# DAC_GainOutputStage4.net
KiCad netlist of a schematic drawn in EAGLE
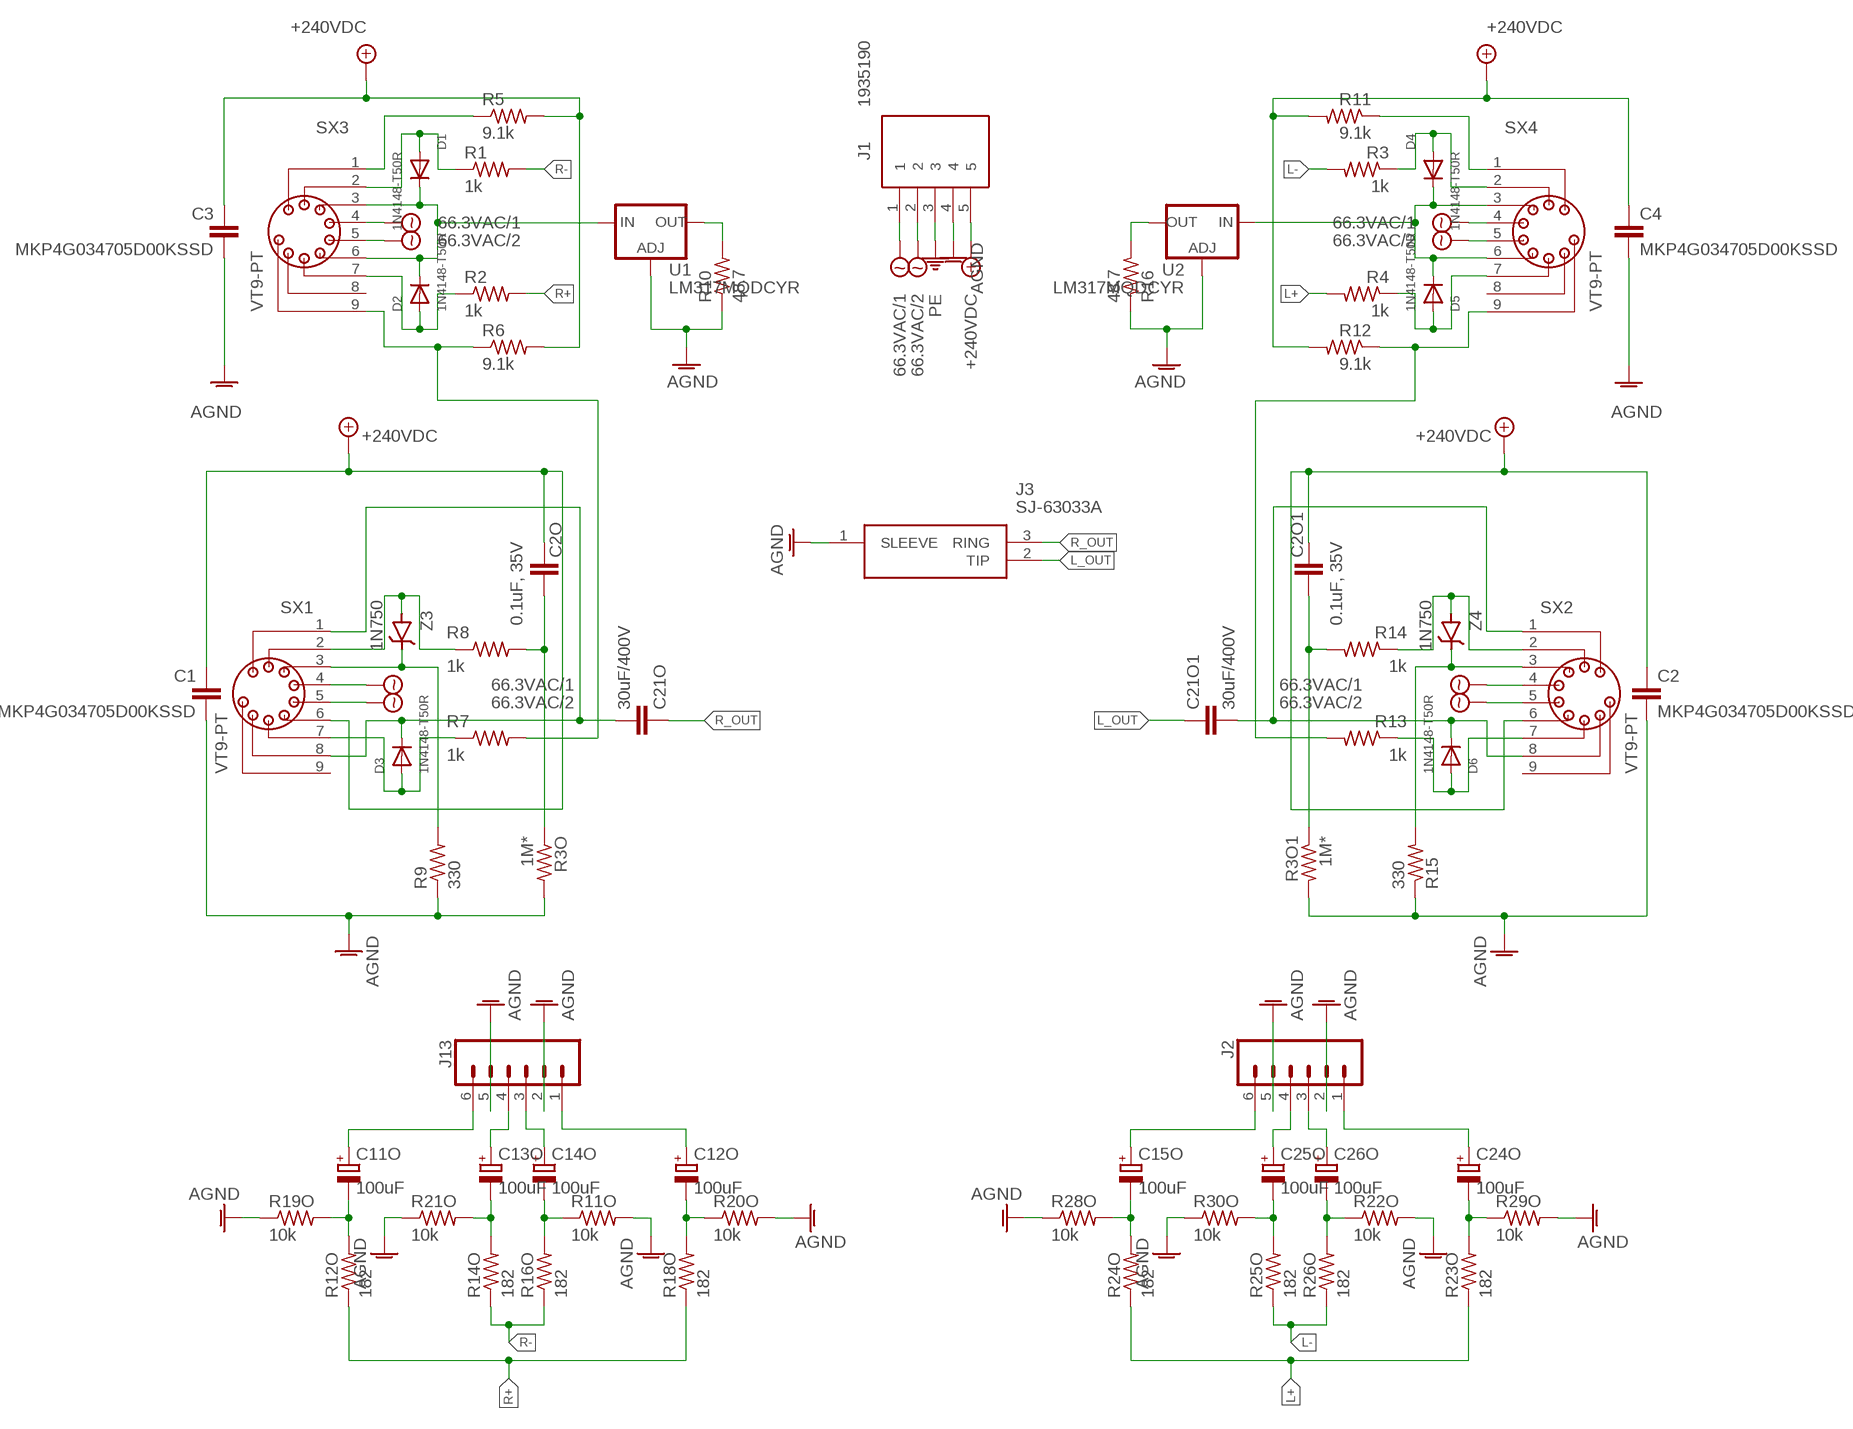
[diagram p0: schematic, sheet 1]

(export (version "E")
  (design (tool "Eeschema 10.0.6"))
  (components
    (comp (ref "C1")
      (value "MKP4G034705D00KSSD")
      (footprint "eagle-import:MKP4G034705D00KSSD")
      (fields (field (name "MOUSER_PART_NUMBER") "505-MKP4G034705DKSSD"))
      (libsource (lib "eagle-import") (part "MKP4G034705D00KSSD"))
    )
    (comp (ref "C2")
      (value "MKP4G034705D00KSSD")
      (footprint "eagle-import:MKP4G034705D00KSSD")
      (fields (field (name "MOUSER_PART_NUMBER") "505-MKP4G034705DKSSD"))
      (libsource (lib "eagle-import") (part "MKP4G034705D00KSSD"))
    )
    (comp (ref "C2O")
      (value "0.1uF, 35V")
      (footprint "eagle-import:MKS4B031002A00JC00")
      (fields
        (field (name "MANUFACTURER_PART_NUMBER") "MKS4B031002A00JC00")
        (field (name "MOUSER_PART_NUMBER") "505-MKS4B0312AJC")
      )
      (libsource (lib "eagle-import") (part "MKS4B031002A00JC00"))
    )
    (comp (ref "C2O1")
      (value "0.1uF, 35V")
      (footprint "eagle-import:MKS4B031002A00JC00")
      (fields
        (field (name "MANUFACTURER_PART_NUMBER") "MKS4B031002A00JC00")
        (field (name "MOUSER_PART_NUMBER") "505-MKS4B0312AJC")
      )
      (libsource (lib "eagle-import") (part "MKS4B031002A00JC00"))
    )
    (comp (ref "C3")
      (value "MKP4G034705D00KSSD")
      (footprint "eagle-import:MKP4G034705D00KSSD")
      (fields (field (name "MOUSER_PART_NUMBER") "505-MKP4G034705DKSSD"))
      (libsource (lib "eagle-import") (part "MKP4G034705D00KSSD"))
    )
    (comp (ref "C4")
      (value "MKP4G034705D00KSSD")
      (footprint "eagle-import:MKP4G034705D00KSSD")
      (fields (field (name "MOUSER_PART_NUMBER") "505-MKP4G034705DKSSD"))
      (libsource (lib "eagle-import") (part "MKP4G034705D00KSSD"))
    )
    (comp (ref "C11O")
      (value "100uF")
      (footprint "eagle-import:CAPPRD350W60D825H1300")
      (fields
        (field (name "ARROW_PART_NUMBER") "UFW1H101MPD1TD")
        (field (name "MOUSER_PART_NUMBER") "647-UFW1H101MPD1TD")
      )
      (libsource (lib "eagle-import") (part "UFW1H101MPD1TD"))
    )
    (comp (ref "C12O")
      (value "100uF")
      (footprint "eagle-import:CAPPRD350W60D825H1300")
      (fields
        (field (name "ARROW_PART_NUMBER") "UFW1H101MPD1TD")
        (field (name "MOUSER_PART_NUMBER") "647-UFW1H101MPD1TD")
      )
      (libsource (lib "eagle-import") (part "UFW1H101MPD1TD"))
    )
    (comp (ref "C13O")
      (value "100uF")
      (footprint "eagle-import:CAPPRD350W60D825H1300")
      (fields
        (field (name "ARROW_PART_NUMBER") "UFW1H101MPD1TD")
        (field (name "MOUSER_PART_NUMBER") "647-UFW1H101MPD1TD")
      )
      (libsource (lib "eagle-import") (part "UFW1H101MPD1TD"))
    )
    (comp (ref "C14O")
      (value "100uF")
      (footprint "eagle-import:CAPPRD350W60D825H1300")
      (fields
        (field (name "ARROW_PART_NUMBER") "UFW1H101MPD1TD")
        (field (name "MOUSER_PART_NUMBER") "647-UFW1H101MPD1TD")
      )
      (libsource (lib "eagle-import") (part "UFW1H101MPD1TD"))
    )
    (comp (ref "C15O")
      (value "100uF")
      (footprint "eagle-import:CAPPRD350W60D825H1300")
      (fields
        (field (name "ARROW_PART_NUMBER") "UFW1H101MPD1TD")
        (field (name "MOUSER_PART_NUMBER") "647-UFW1H101MPD1TD")
      )
      (libsource (lib "eagle-import") (part "UFW1H101MPD1TD"))
    )
    (comp (ref "C21O")
      (value "30uF/400V")
      (footprint "eagle-import:DCP4G053006ID2KSSD")
      (fields
        (field (name "MANUFACTURER_PART_NUMBER") "DCP4G053006ID2KSSD")
        (field (name "MOUSER_PART_NUMBER") "505-DCP4G0536ID2KSSD")
      )
      (libsource (lib "eagle-import") (part "DCP4G053006ID2KSSD"))
    )
    (comp (ref "C21O1")
      (value "30uF/400V")
      (footprint "eagle-import:DCP4G053006ID2KSSD")
      (fields
        (field (name "MANUFACTURER_PART_NUMBER") "DCP4G053006ID2KSSD")
        (field (name "MOUSER_PART_NUMBER") "505-DCP4G0536ID2KSSD")
      )
      (libsource (lib "eagle-import") (part "DCP4G053006ID2KSSD"))
    )
    (comp (ref "C24O")
      (value "100uF")
      (footprint "eagle-import:CAPPRD350W60D825H1300")
      (fields
        (field (name "ARROW_PART_NUMBER") "UFW1H101MPD1TD")
        (field (name "MOUSER_PART_NUMBER") "647-UFW1H101MPD1TD")
      )
      (libsource (lib "eagle-import") (part "UFW1H101MPD1TD"))
    )
    (comp (ref "C25O")
      (value "100uF")
      (footprint "eagle-import:CAPPRD350W60D825H1300")
      (fields
        (field (name "ARROW_PART_NUMBER") "UFW1H101MPD1TD")
        (field (name "MOUSER_PART_NUMBER") "647-UFW1H101MPD1TD")
      )
      (libsource (lib "eagle-import") (part "UFW1H101MPD1TD"))
    )
    (comp (ref "C26O")
      (value "100uF")
      (footprint "eagle-import:CAPPRD350W60D825H1300")
      (fields
        (field (name "ARROW_PART_NUMBER") "UFW1H101MPD1TD")
        (field (name "MOUSER_PART_NUMBER") "647-UFW1H101MPD1TD")
      )
      (libsource (lib "eagle-import") (part "UFW1H101MPD1TD"))
    )
    (comp (ref "D1")
      (value "1N4148-T50R")
      (footprint "eagle-import:DIOAD1068W53L380D172")
      (fields (field (name "MOUSER_PART_NUMBER") "512-1N4148T50R"))
      (libsource (lib "eagle-import") (part "1N4148-T50R"))
    )
    (comp (ref "D2")
      (value "1N4148-T50R")
      (footprint "eagle-import:DIOAD1068W53L380D172")
      (fields (field (name "MOUSER_PART_NUMBER") "512-1N4148T50R"))
      (libsource (lib "eagle-import") (part "1N4148-T50R"))
    )
    (comp (ref "D3")
      (value "1N4148-T50R")
      (footprint "eagle-import:DIOAD1068W53L380D172")
      (fields (field (name "MOUSER_PART_NUMBER") "512-1N4148T50R"))
      (libsource (lib "eagle-import") (part "1N4148-T50R"))
    )
    (comp (ref "D4")
      (value "1N4148-T50R")
      (footprint "eagle-import:DIOAD1068W53L380D172")
      (fields (field (name "MOUSER_PART_NUMBER") "512-1N4148T50R"))
      (libsource (lib "eagle-import") (part "1N4148-T50R"))
    )
    (comp (ref "D5")
      (value "1N4148-T50R")
      (footprint "eagle-import:DIOAD1068W53L380D172")
      (fields (field (name "MOUSER_PART_NUMBER") "512-1N4148T50R"))
      (libsource (lib "eagle-import") (part "1N4148-T50R"))
    )
    (comp (ref "D6")
      (value "1N4148-T50R")
      (footprint "eagle-import:DIOAD1068W53L380D172")
      (fields (field (name "MOUSER_PART_NUMBER") "512-1N4148T50R"))
      (libsource (lib "eagle-import") (part "1N4148-T50R"))
    )
    (comp (ref "J1")
      (value "1935190")
      (footprint "eagle-import:1935190")
      (fields (field (name "MOUSER_PART_NUMBER") "651-1935190"))
      (libsource (lib "eagle-import") (part "1935190"))
    )
    (comp (ref "J2")
      (value "CONN_06SILK_FEMALE_PTH")
      (footprint "eagle-import:1X06")
      (libsource (lib "eagle-import") (part "CONN_06SILK_FEMALE_PTH"))
    )
    (comp (ref "J3")
      (value "SJ-63033A")
      (footprint "eagle-import:SJ63033A")
      (libsource (lib "eagle-import") (part "SJ-63033A"))
    )
    (comp (ref "J13")
      (value "CONN_06SILK_FEMALE_PTH")
      (footprint "eagle-import:1X06")
      (libsource (lib "eagle-import") (part "CONN_06SILK_FEMALE_PTH"))
    )
    (comp (ref "R1")
      (value "1k")
      (footprint "eagle-import:0207_10")
      (fields
        (field (name "MANUFACTURER_PART_NUMBER") "LR1F1K0")
        (field (name "MOUSER_PART_NUMBER") "279-LR1F1K0")
      )
      (libsource (lib "eagle-import") (part "LR1F1K0"))
    )
    (comp (ref "R2")
      (value "1k")
      (footprint "eagle-import:0207_10")
      (fields
        (field (name "MANUFACTURER_PART_NUMBER") "LR1F1K0")
        (field (name "MOUSER_PART_NUMBER") "279-LR1F1K0")
      )
      (libsource (lib "eagle-import") (part "LR1F1K0"))
    )
    (comp (ref "R3")
      (value "1k")
      (footprint "eagle-import:0207_10")
      (fields
        (field (name "MANUFACTURER_PART_NUMBER") "LR1F1K0")
        (field (name "MOUSER_PART_NUMBER") "279-LR1F1K0")
      )
      (libsource (lib "eagle-import") (part "LR1F1K0"))
    )
    (comp (ref "R3O")
      (value "1M*")
      (footprint "eagle-import:0207_10")
      (fields
        (field (name "MANUFACTURER_PART_NUMBER") "LR1F1M0")
        (field (name "MOUSER_PART_NUMBER") "279-LR1F1M0")
      )
      (libsource (lib "eagle-import") (part "LR1F1M0"))
    )
    (comp (ref "R3O1")
      (value "1M*")
      (footprint "eagle-import:0207_10")
      (fields
        (field (name "MANUFACTURER_PART_NUMBER") "LR1F1M0")
        (field (name "MOUSER_PART_NUMBER") "279-LR1F1M0")
      )
      (libsource (lib "eagle-import") (part "LR1F1M0"))
    )
    (comp (ref "R4")
      (value "1k")
      (footprint "eagle-import:0207_10")
      (fields
        (field (name "MANUFACTURER_PART_NUMBER") "LR1F1K0")
        (field (name "MOUSER_PART_NUMBER") "279-LR1F1K0")
      )
      (libsource (lib "eagle-import") (part "LR1F1K0"))
    )
    (comp (ref "R5")
      (value "9.1k")
      (footprint "eagle-import:0411_15")
      (fields
        (field (name "MANUFACTURER_PART_NUMBER") "PR02000209101FA100")
        (field (name "MOUSER_PART_NUMBER") "594-PR02000209101FA1")
      )
      (libsource (lib "eagle-import") (part "PR02000209101FA100"))
    )
    (comp (ref "R6")
      (value "9.1k")
      (footprint "eagle-import:0411_15")
      (fields
        (field (name "MANUFACTURER_PART_NUMBER") "PR02000209101FA100")
        (field (name "MOUSER_PART_NUMBER") "594-PR02000209101FA1")
      )
      (libsource (lib "eagle-import") (part "PR02000209101FA100"))
    )
    (comp (ref "R7")
      (value "1k")
      (footprint "eagle-import:0207_10")
      (fields
        (field (name "MANUFACTURER_PART_NUMBER") "LR1F1K0")
        (field (name "MOUSER_PART_NUMBER") "279-LR1F1K0")
      )
      (libsource (lib "eagle-import") (part "LR1F1K0"))
    )
    (comp (ref "R8")
      (value "1k")
      (footprint "eagle-import:0207_10")
      (fields
        (field (name "MANUFACTURER_PART_NUMBER") "LR1F1K0")
        (field (name "MOUSER_PART_NUMBER") "279-LR1F1K0")
      )
      (libsource (lib "eagle-import") (part "LR1F1K0"))
    )
    (comp (ref "R9")
      (value "330")
      (footprint "eagle-import:0207_10")
      (fields
        (field (name "MANUFACTURER_PART_NUMBER") "LR1F330R")
        (field (name "MOUSER_PART_NUMBER") "279-LR1F330R")
      )
      (libsource (lib "eagle-import") (part "LR1F330R"))
    )
    (comp (ref "R10")
      (value "48.7")
      (footprint "eagle-import:0207_10")
      (fields
        (field (name "MANUFACTURER_PART_NUMBER") "RN55D48R7FB14")
        (field (name "MOUSER_PART_NUMBER") "71-RN55D-F-48.7")
      )
      (libsource (lib "eagle-import") (part "RN55D48R7FB14"))
    )
    (comp (ref "R11")
      (value "9.1k")
      (footprint "eagle-import:0411_15")
      (fields
        (field (name "MANUFACTURER_PART_NUMBER") "PR02000209101FA100")
        (field (name "MOUSER_PART_NUMBER") "594-PR02000209101FA1")
      )
      (libsource (lib "eagle-import") (part "PR02000209101FA100"))
    )
    (comp (ref "R11O")
      (value "10k")
      (footprint "eagle-import:0207_10")
      (fields
        (field (name "MANUFACTURER_PART_NUMBER") "LR1F10K")
        (field (name "MOUSER_PART_NUMBER") "279-LR1F10K")
      )
      (libsource (lib "eagle-import") (part "LR1F10K"))
    )
    (comp (ref "R12")
      (value "9.1k")
      (footprint "eagle-import:0411_15")
      (fields
        (field (name "MANUFACTURER_PART_NUMBER") "PR02000209101FA100")
        (field (name "MOUSER_PART_NUMBER") "594-PR02000209101FA1")
      )
      (libsource (lib "eagle-import") (part "PR02000209101FA100"))
    )
    (comp (ref "R12O")
      (value "182")
      (footprint "eagle-import:0207_10")
      (fields
        (field (name "MANUFACTURER") "Yageo")
        (field (name "MANUFACTURER_PART_NUMBER") "MF0207FTE52-182R")
        (field (name "MOUSER_PART_NUMBER") "603-MF0207FTE52-182R")
      )
      (libsource (lib "eagle-import") (part "MF0207FTE52-182R"))
    )
    (comp (ref "R13")
      (value "1k")
      (footprint "eagle-import:0207_10")
      (fields
        (field (name "MANUFACTURER_PART_NUMBER") "LR1F1K0")
        (field (name "MOUSER_PART_NUMBER") "279-LR1F1K0")
      )
      (libsource (lib "eagle-import") (part "LR1F1K0"))
    )
    (comp (ref "R14")
      (value "1k")
      (footprint "eagle-import:0207_10")
      (fields
        (field (name "MANUFACTURER_PART_NUMBER") "LR1F1K0")
        (field (name "MOUSER_PART_NUMBER") "279-LR1F1K0")
      )
      (libsource (lib "eagle-import") (part "LR1F1K0"))
    )
    (comp (ref "R14O")
      (value "182")
      (footprint "eagle-import:0207_10")
      (fields
        (field (name "MANUFACTURER") "Yageo")
        (field (name "MANUFACTURER_PART_NUMBER") "MF0207FTE52-182R")
        (field (name "MOUSER_PART_NUMBER") "603-MF0207FTE52-182R")
      )
      (libsource (lib "eagle-import") (part "MF0207FTE52-182R"))
    )
    (comp (ref "R15")
      (value "330")
      (footprint "eagle-import:0207_10")
      (fields
        (field (name "MANUFACTURER_PART_NUMBER") "LR1F330R")
        (field (name "MOUSER_PART_NUMBER") "279-LR1F330R")
      )
      (libsource (lib "eagle-import") (part "LR1F330R"))
    )
    (comp (ref "R16")
      (value "48.7")
      (footprint "eagle-import:0207_10")
      (fields
        (field (name "MANUFACTURER_PART_NUMBER") "RN55D48R7FB14")
        (field (name "MOUSER_PART_NUMBER") "71-RN55D-F-48.7")
      )
      (libsource (lib "eagle-import") (part "RN55D48R7FB14"))
    )
    (comp (ref "R16O")
      (value "182")
      (footprint "eagle-import:0207_10")
      (fields
        (field (name "MANUFACTURER") "Yageo")
        (field (name "MANUFACTURER_PART_NUMBER") "MF0207FTE52-182R")
        (field (name "MOUSER_PART_NUMBER") "603-MF0207FTE52-182R")
      )
      (libsource (lib "eagle-import") (part "MF0207FTE52-182R"))
    )
    (comp (ref "R18O")
      (value "182")
      (footprint "eagle-import:0207_10")
      (fields
        (field (name "MANUFACTURER") "Yageo")
        (field (name "MANUFACTURER_PART_NUMBER") "MF0207FTE52-182R")
        (field (name "MOUSER_PART_NUMBER") "603-MF0207FTE52-182R")
      )
      (libsource (lib "eagle-import") (part "MF0207FTE52-182R"))
    )
    (comp (ref "R19O")
      (value "10k")
      (footprint "eagle-import:0207_10")
      (fields
        (field (name "MANUFACTURER_PART_NUMBER") "LR1F10K")
        (field (name "MOUSER_PART_NUMBER") "279-LR1F10K")
      )
      (libsource (lib "eagle-import") (part "LR1F10K"))
    )
    (comp (ref "R20O")
      (value "10k")
      (footprint "eagle-import:0207_10")
      (fields
        (field (name "MANUFACTURER_PART_NUMBER") "LR1F10K")
        (field (name "MOUSER_PART_NUMBER") "279-LR1F10K")
      )
      (libsource (lib "eagle-import") (part "LR1F10K"))
    )
    (comp (ref "R21O")
      (value "10k")
      (footprint "eagle-import:0207_10")
      (fields
        (field (name "MANUFACTURER_PART_NUMBER") "LR1F10K")
        (field (name "MOUSER_PART_NUMBER") "279-LR1F10K")
      )
      (libsource (lib "eagle-import") (part "LR1F10K"))
    )
    (comp (ref "R22O")
      (value "10k")
      (footprint "eagle-import:0207_10")
      (fields
        (field (name "MANUFACTURER_PART_NUMBER") "LR1F10K")
        (field (name "MOUSER_PART_NUMBER") "279-LR1F10K")
      )
      (libsource (lib "eagle-import") (part "LR1F10K"))
    )
    (comp (ref "R23O")
      (value "182")
      (footprint "eagle-import:0207_10")
      (fields
        (field (name "MANUFACTURER") "Yageo")
        (field (name "MANUFACTURER_PART_NUMBER") "MF0207FTE52-182R")
        (field (name "MOUSER_PART_NUMBER") "603-MF0207FTE52-182R")
      )
      (libsource (lib "eagle-import") (part "MF0207FTE52-182R"))
    )
    (comp (ref "R24O")
      (value "182")
      (footprint "eagle-import:0207_10")
      (fields
        (field (name "MANUFACTURER") "Yageo")
        (field (name "MANUFACTURER_PART_NUMBER") "MF0207FTE52-182R")
        (field (name "MOUSER_PART_NUMBER") "603-MF0207FTE52-182R")
      )
      (libsource (lib "eagle-import") (part "MF0207FTE52-182R"))
    )
    (comp (ref "R25O")
      (value "182")
      (footprint "eagle-import:0207_10")
      (fields
        (field (name "MANUFACTURER") "Yageo")
        (field (name "MANUFACTURER_PART_NUMBER") "MF0207FTE52-182R")
        (field (name "MOUSER_PART_NUMBER") "603-MF0207FTE52-182R")
      )
      (libsource (lib "eagle-import") (part "MF0207FTE52-182R"))
    )
    (comp (ref "R26O")
      (value "182")
      (footprint "eagle-import:0207_10")
      (fields
        (field (name "MANUFACTURER") "Yageo")
        (field (name "MANUFACTURER_PART_NUMBER") "MF0207FTE52-182R")
        (field (name "MOUSER_PART_NUMBER") "603-MF0207FTE52-182R")
      )
      (libsource (lib "eagle-import") (part "MF0207FTE52-182R"))
    )
    (comp (ref "R28O")
      (value "10k")
      (footprint "eagle-import:0207_10")
      (fields
        (field (name "MANUFACTURER_PART_NUMBER") "LR1F10K")
        (field (name "MOUSER_PART_NUMBER") "279-LR1F10K")
      )
      (libsource (lib "eagle-import") (part "LR1F10K"))
    )
    (comp (ref "R29O")
      (value "10k")
      (footprint "eagle-import:0207_10")
      (fields
        (field (name "MANUFACTURER_PART_NUMBER") "LR1F10K")
        (field (name "MOUSER_PART_NUMBER") "279-LR1F10K")
      )
      (libsource (lib "eagle-import") (part "LR1F10K"))
    )
    (comp (ref "R30O")
      (value "10k")
      (footprint "eagle-import:0207_10")
      (fields
        (field (name "MANUFACTURER_PART_NUMBER") "LR1F10K")
        (field (name "MOUSER_PART_NUMBER") "279-LR1F10K")
      )
      (libsource (lib "eagle-import") (part "LR1F10K"))
    )
    (comp (ref "SX1")
      (value "VT9-PT")
      (footprint "eagle-import:VT9-PT")
      (libsource (lib "eagle-import") (part "VT9-PT"))
    )
    (comp (ref "SX2")
      (value "VT9-PT")
      (footprint "eagle-import:VT9-PT")
      (libsource (lib "eagle-import") (part "VT9-PT"))
    )
    (comp (ref "SX3")
      (value "VT9-PT")
      (footprint "eagle-import:VT9-PT")
      (libsource (lib "eagle-import") (part "VT9-PT"))
    )
    (comp (ref "SX4")
      (value "VT9-PT")
      (footprint "eagle-import:VT9-PT")
      (libsource (lib "eagle-import") (part "VT9-PT"))
    )
    (comp (ref "U1")
      (value "LM317MQDCYR")
      (footprint "eagle-import:SOT230P700X180-4N")
      (fields (field (name "MOUSER_PART_NUMBER") "595-LM317MQDCYR"))
      (libsource (lib "eagle-import") (part "LM317MQDCYR"))
    )
    (comp (ref "U2")
      (value "LM317MQDCYR")
      (footprint "eagle-import:SOT230P700X180-4N")
      (fields (field (name "MOUSER_PART_NUMBER") "595-LM317MQDCYR"))
      (libsource (lib "eagle-import") (part "LM317MQDCYR"))
    )
    (comp (ref "Z3")
      (value "1N750")
      (footprint "eagle-import:DIOAD1256W56L444D203")
      (fields (field (name "MOUSER_PART_NUMBER") "494-1N750(DO-35)"))
      (libsource (lib "eagle-import") (part "1N750"))
    )
    (comp (ref "Z4")
      (value "1N750")
      (footprint "eagle-import:DIOAD1256W56L444D203")
      (fields (field (name "MOUSER_PART_NUMBER") "494-1N750(DO-35)"))
      (libsource (lib "eagle-import") (part "1N750"))
    )
  )
  (nets
    (net (code "1") (name "+240VDC") (class "Default")
      (node (ref "C1") (pin "1") (pinfunction "1_1") (pintype "passive"))
      (node (ref "C2") (pin "1") (pinfunction "1_1") (pintype "passive"))
      (node (ref "C2O") (pin "1") (pinfunction "1_1") (pintype "passive"))
      (node (ref "C2O1") (pin "1") (pinfunction "1_1") (pintype "passive"))
      (node (ref "C3") (pin "1") (pinfunction "1_1") (pintype "passive"))
      (node (ref "C4") (pin "1") (pinfunction "1_1") (pintype "passive"))
      (node (ref "J1") (pin "5") (pinfunction "5_5") (pintype "bidirectional"))
      (node (ref "R11") (pin "2") (pinfunction "2_2") (pintype "passive"))
      (node (ref "R12") (pin "2") (pinfunction "2_2") (pintype "passive"))
      (node (ref "R5") (pin "2") (pinfunction "2_2") (pintype "passive"))
      (node (ref "R6") (pin "2") (pinfunction "2_2") (pintype "passive"))
      (node (ref "SX1") (pin "6") (pinfunction "6_6") (pintype "passive"))
      (node (ref "SX2") (pin "6") (pinfunction "6_6") (pintype "passive"))
    )
    (net (code "2") (name "66.3VAC{slash}1") (class "Default")
      (node (ref "J1") (pin "1") (pinfunction "1_1") (pintype "bidirectional"))
      (node (ref "SX1") (pin "4") (pinfunction "4_4") (pintype "passive"))
      (node (ref "SX2") (pin "4") (pinfunction "4_4") (pintype "passive"))
      (node (ref "SX3") (pin "4") (pinfunction "4_4") (pintype "passive"))
      (node (ref "SX4") (pin "4") (pinfunction "4_4") (pintype "passive"))
    )
    (net (code "3") (name "66.3VAC{slash}2") (class "Default")
      (node (ref "J1") (pin "2") (pinfunction "2_2") (pintype "bidirectional"))
      (node (ref "SX1") (pin "5") (pinfunction "5_5") (pintype "passive"))
      (node (ref "SX2") (pin "5") (pinfunction "5_5") (pintype "passive"))
      (node (ref "SX3") (pin "5") (pinfunction "5_5") (pintype "passive"))
      (node (ref "SX4") (pin "5") (pinfunction "5_5") (pintype "passive"))
    )
    (net (code "4") (name "AGND") (class "Default")
      (node (ref "C1") (pin "2") (pinfunction "2_2") (pintype "passive"))
      (node (ref "C2") (pin "2") (pinfunction "2_2") (pintype "passive"))
      (node (ref "C3") (pin "2") (pinfunction "2_2") (pintype "passive"))
      (node (ref "C4") (pin "2") (pinfunction "2_2") (pintype "passive"))
      (node (ref "J1") (pin "4") (pinfunction "4_4") (pintype "bidirectional"))
      (node (ref "J13") (pin "2") (pinfunction "2_2") (pintype "passive"))
      (node (ref "J13") (pin "5") (pinfunction "5_5") (pintype "passive"))
      (node (ref "J2") (pin "2") (pinfunction "2_2") (pintype "passive"))
      (node (ref "J2") (pin "5") (pinfunction "5_5") (pintype "passive"))
      (node (ref "J3") (pin "1") (pinfunction "SLEEVE_1") (pintype "bidirectional"))
      (node (ref "R10") (pin "1") (pinfunction "1_1") (pintype "passive"))
      (node (ref "R11O") (pin "2") (pinfunction "2_2") (pintype "passive"))
      (node (ref "R15") (pin "1") (pinfunction "1_1") (pintype "passive"))
      (node (ref "R16") (pin "1") (pinfunction "1_1") (pintype "passive"))
      (node (ref "R19O") (pin "1") (pinfunction "1_1") (pintype "passive"))
      (node (ref "R20O") (pin "2") (pinfunction "2_2") (pintype "passive"))
      (node (ref "R21O") (pin "1") (pinfunction "1_1") (pintype "passive"))
      (node (ref "R22O") (pin "2") (pinfunction "2_2") (pintype "passive"))
      (node (ref "R28O") (pin "1") (pinfunction "1_1") (pintype "passive"))
      (node (ref "R29O") (pin "2") (pinfunction "2_2") (pintype "passive"))
      (node (ref "R30O") (pin "1") (pinfunction "1_1") (pintype "passive"))
      (node (ref "R3O") (pin "2") (pinfunction "2_2") (pintype "passive"))
      (node (ref "R3O1") (pin "2") (pinfunction "2_2") (pintype "passive"))
      (node (ref "R9") (pin "1") (pinfunction "1_1") (pintype "passive"))
      (node (ref "U1") (pin "1") (pinfunction "ADJ_1") (pintype "input"))
      (node (ref "U2") (pin "1") (pinfunction "ADJ_1") (pintype "input"))
    )
    (net (code "5") (name "L+") (class "Default")
      (node (ref "R23O") (pin "1") (pinfunction "1_1") (pintype "passive"))
      (node (ref "R24O") (pin "1") (pinfunction "1_1") (pintype "passive"))
      (node (ref "R4") (pin "2") (pinfunction "2_2") (pintype "passive"))
    )
    (net (code "6") (name "L-") (class "Default")
      (node (ref "R25O") (pin "1") (pinfunction "1_1") (pintype "passive"))
      (node (ref "R26O") (pin "1") (pinfunction "1_1") (pintype "passive"))
      (node (ref "R3") (pin "2") (pinfunction "2_2") (pintype "passive"))
    )
    (net (code "7") (name "L_OUT") (class "Default")
      (node (ref "C21O1") (pin "1") (pinfunction "1_1") (pintype "passive"))
      (node (ref "J3") (pin "2") (pinfunction "TIP_2") (pintype "bidirectional"))
    )
    (net (code "8") (name "Net-(C2O-Pad2)") (class "Default")
      (node (ref "C2O") (pin "2") (pinfunction "2_2") (pintype "passive"))
      (node (ref "R3O") (pin "1") (pinfunction "1_1") (pintype "passive"))
      (node (ref "R8") (pin "2") (pinfunction "2_2") (pintype "passive"))
    )
    (net (code "9") (name "Net-(C2O1-Pad2)") (class "Default")
      (node (ref "C2O1") (pin "2") (pinfunction "2_2") (pintype "passive"))
      (node (ref "R14") (pin "2") (pinfunction "2_2") (pintype "passive"))
      (node (ref "R3O1") (pin "1") (pinfunction "1_1") (pintype "passive"))
    )
    (net (code "10") (name "Net-(C11O-+)") (class "Default")
      (node (ref "C11O") (pin "1") (pinfunction "+_1") (pintype "passive"))
      (node (ref "J13") (pin "6") (pinfunction "6_6") (pintype "passive"))
    )
    (net (code "11") (name "Net-(C11O--)") (class "Default")
      (node (ref "C11O") (pin "2") (pinfunction "-_2") (pintype "passive"))
      (node (ref "R12O") (pin "2") (pinfunction "2_2") (pintype "passive"))
      (node (ref "R19O") (pin "2") (pinfunction "2_2") (pintype "passive"))
    )
    (net (code "12") (name "Net-(C12O-+)") (class "Default")
      (node (ref "C12O") (pin "1") (pinfunction "+_1") (pintype "passive"))
      (node (ref "J13") (pin "1") (pinfunction "1_1") (pintype "passive"))
    )
    (net (code "13") (name "Net-(C12O--)") (class "Default")
      (node (ref "C12O") (pin "2") (pinfunction "-_2") (pintype "passive"))
      (node (ref "R18O") (pin "2") (pinfunction "2_2") (pintype "passive"))
      (node (ref "R20O") (pin "1") (pinfunction "1_1") (pintype "passive"))
    )
    (net (code "14") (name "Net-(C13O-+)") (class "Default")
      (node (ref "C13O") (pin "1") (pinfunction "+_1") (pintype "passive"))
      (node (ref "J13") (pin "4") (pinfunction "4_4") (pintype "passive"))
    )
    (net (code "15") (name "Net-(C13O--)") (class "Default")
      (node (ref "C13O") (pin "2") (pinfunction "-_2") (pintype "passive"))
      (node (ref "R14O") (pin "2") (pinfunction "2_2") (pintype "passive"))
      (node (ref "R21O") (pin "2") (pinfunction "2_2") (pintype "passive"))
    )
    (net (code "16") (name "Net-(C14O-+)") (class "Default")
      (node (ref "C14O") (pin "1") (pinfunction "+_1") (pintype "passive"))
      (node (ref "J13") (pin "3") (pinfunction "3_3") (pintype "passive"))
    )
    (net (code "17") (name "Net-(C14O--)") (class "Default")
      (node (ref "C14O") (pin "2") (pinfunction "-_2") (pintype "passive"))
      (node (ref "R11O") (pin "1") (pinfunction "1_1") (pintype "passive"))
      (node (ref "R16O") (pin "2") (pinfunction "2_2") (pintype "passive"))
    )
    (net (code "18") (name "Net-(C15O-+)") (class "Default")
      (node (ref "C15O") (pin "1") (pinfunction "+_1") (pintype "passive"))
      (node (ref "J2") (pin "6") (pinfunction "6_6") (pintype "passive"))
    )
    (net (code "19") (name "Net-(C15O--)") (class "Default")
      (node (ref "C15O") (pin "2") (pinfunction "-_2") (pintype "passive"))
      (node (ref "R24O") (pin "2") (pinfunction "2_2") (pintype "passive"))
      (node (ref "R28O") (pin "2") (pinfunction "2_2") (pintype "passive"))
    )
    (net (code "20") (name "Net-(C24O-+)") (class "Default")
      (node (ref "C24O") (pin "1") (pinfunction "+_1") (pintype "passive"))
      (node (ref "J2") (pin "1") (pinfunction "1_1") (pintype "passive"))
    )
    (net (code "21") (name "Net-(C24O--)") (class "Default")
      (node (ref "C24O") (pin "2") (pinfunction "-_2") (pintype "passive"))
      (node (ref "R23O") (pin "2") (pinfunction "2_2") (pintype "passive"))
      (node (ref "R29O") (pin "1") (pinfunction "1_1") (pintype "passive"))
    )
    (net (code "22") (name "Net-(C25O-+)") (class "Default")
      (node (ref "C25O") (pin "1") (pinfunction "+_1") (pintype "passive"))
      (node (ref "J2") (pin "4") (pinfunction "4_4") (pintype "passive"))
    )
    (net (code "23") (name "Net-(C25O--)") (class "Default")
      (node (ref "C25O") (pin "2") (pinfunction "-_2") (pintype "passive"))
      (node (ref "R25O") (pin "2") (pinfunction "2_2") (pintype "passive"))
      (node (ref "R30O") (pin "2") (pinfunction "2_2") (pintype "passive"))
    )
    (net (code "24") (name "Net-(C26O-+)") (class "Default")
      (node (ref "C26O") (pin "1") (pinfunction "+_1") (pintype "passive"))
      (node (ref "J2") (pin "3") (pinfunction "3_3") (pintype "passive"))
    )
    (net (code "25") (name "Net-(C26O--)") (class "Default")
      (node (ref "C26O") (pin "2") (pinfunction "-_2") (pintype "passive"))
      (node (ref "R22O") (pin "1") (pinfunction "1_1") (pintype "passive"))
      (node (ref "R26O") (pin "2") (pinfunction "2_2") (pintype "passive"))
    )
    (net (code "26") (name "Net-(D1-A)") (class "Default")
      (node (ref "D1") (pin "2") (pinfunction "A_2") (pintype "passive"))
      (node (ref "R1") (pin "1") (pinfunction "1_1") (pintype "passive"))
      (node (ref "SX3") (pin "2") (pinfunction "2_2") (pintype "passive"))
    )
    (net (code "27") (name "Net-(D1-C)") (class "Default")
      (node (ref "D1") (pin "1") (pinfunction "C_1") (pintype "passive"))
      (node (ref "D2") (pin "1") (pinfunction "C_1") (pintype "passive"))
      (node (ref "SX3") (pin "3") (pinfunction "3_3") (pintype "passive"))
      (node (ref "SX3") (pin "6") (pinfunction "6_6") (pintype "passive"))
      (node (ref "U1") (pin "3") (pinfunction "IN_3") (pintype "input"))
    )
    (net (code "28") (name "Net-(D2-A)") (class "Default")
      (node (ref "D2") (pin "2") (pinfunction "A_2") (pintype "passive"))
      (node (ref "R2") (pin "1") (pinfunction "1_1") (pintype "passive"))
      (node (ref "SX3") (pin "7") (pinfunction "7_7") (pintype "passive"))
    )
    (net (code "29") (name "Net-(D3-A)") (class "Default")
      (node (ref "D3") (pin "2") (pinfunction "A_2") (pintype "passive"))
      (node (ref "R7") (pin "1") (pinfunction "1_1") (pintype "passive"))
      (node (ref "SX1") (pin "7") (pinfunction "7_7") (pintype "passive"))
    )
    (net (code "30") (name "Net-(D3-C)") (class "Default")
      (node (ref "C21O") (pin "2") (pinfunction "2_2") (pintype "passive"))
      (node (ref "D3") (pin "1") (pinfunction "C_1") (pintype "passive"))
      (node (ref "SX1") (pin "1") (pinfunction "1_1") (pintype "passive"))
      (node (ref "SX1") (pin "8") (pinfunction "8_8") (pintype "passive"))
    )
    (net (code "31") (name "Net-(D4-A)") (class "Default")
      (node (ref "D4") (pin "2") (pinfunction "A_2") (pintype "passive"))
      (node (ref "R3") (pin "1") (pinfunction "1_1") (pintype "passive"))
      (node (ref "SX4") (pin "2") (pinfunction "2_2") (pintype "passive"))
    )
    (net (code "32") (name "Net-(D4-C)") (class "Default")
      (node (ref "D4") (pin "1") (pinfunction "C_1") (pintype "passive"))
      (node (ref "D5") (pin "1") (pinfunction "C_1") (pintype "passive"))
      (node (ref "SX4") (pin "3") (pinfunction "3_3") (pintype "passive"))
      (node (ref "SX4") (pin "6") (pinfunction "6_6") (pintype "passive"))
      (node (ref "U2") (pin "3") (pinfunction "IN_3") (pintype "input"))
    )
    (net (code "33") (name "Net-(D5-A)") (class "Default")
      (node (ref "D5") (pin "2") (pinfunction "A_2") (pintype "passive"))
      (node (ref "R4") (pin "1") (pinfunction "1_1") (pintype "passive"))
      (node (ref "SX4") (pin "7") (pinfunction "7_7") (pintype "passive"))
    )
    (net (code "34") (name "Net-(D6-A)") (class "Default")
      (node (ref "D6") (pin "2") (pinfunction "A_2") (pintype "passive"))
      (node (ref "R13") (pin "1") (pinfunction "1_1") (pintype "passive"))
      (node (ref "SX2") (pin "7") (pinfunction "7_7") (pintype "passive"))
    )
    (net (code "35") (name "Net-(D6-C)") (class "Default")
      (node (ref "C21O1") (pin "2") (pinfunction "2_2") (pintype "passive"))
      (node (ref "D6") (pin "1") (pinfunction "C_1") (pintype "passive"))
      (node (ref "SX2") (pin "1") (pinfunction "1_1") (pintype "passive"))
      (node (ref "SX2") (pin "8") (pinfunction "8_8") (pintype "passive"))
    )
    (net (code "36") (name "Net-(R5-Pad1)") (class "Default")
      (node (ref "R5") (pin "1") (pinfunction "1_1") (pintype "passive"))
      (node (ref "SX3") (pin "1") (pinfunction "1_1") (pintype "passive"))
    )
    (net (code "37") (name "Net-(R6-Pad1)") (class "Default")
      (node (ref "R6") (pin "1") (pinfunction "1_1") (pintype "passive"))
      (node (ref "R7") (pin "2") (pinfunction "2_2") (pintype "passive"))
      (node (ref "SX3") (pin "9") (pinfunction "9_9") (pintype "passive"))
    )
    (net (code "38") (name "Net-(R10-Pad2)") (class "Default")
      (node (ref "R10") (pin "2") (pinfunction "2_2") (pintype "passive"))
      (node (ref "U1") (pin "2") (pinfunction "OUT_2") (pintype "passive"))
      (node (ref "U1") (pin "4") (pinfunction "OUT_4") (pintype "passive"))
    )
    (net (code "39") (name "Net-(R11-Pad1)") (class "Default")
      (node (ref "R11") (pin "1") (pinfunction "1_1") (pintype "passive"))
      (node (ref "SX4") (pin "1") (pinfunction "1_1") (pintype "passive"))
    )
    (net (code "40") (name "Net-(R12-Pad1)") (class "Default")
      (node (ref "R12") (pin "1") (pinfunction "1_1") (pintype "passive"))
      (node (ref "R13") (pin "2") (pinfunction "2_2") (pintype "passive"))
      (node (ref "SX4") (pin "9") (pinfunction "9_9") (pintype "passive"))
    )
    (net (code "41") (name "Net-(R16-Pad2)") (class "Default")
      (node (ref "R16") (pin "2") (pinfunction "2_2") (pintype "passive"))
      (node (ref "U2") (pin "2") (pinfunction "OUT_2") (pintype "passive"))
      (node (ref "U2") (pin "4") (pinfunction "OUT_4") (pintype "passive"))
    )
    (net (code "42") (name "Net-(Z3-A)") (class "Default")
      (node (ref "R8") (pin "1") (pinfunction "1_1") (pintype "passive"))
      (node (ref "SX1") (pin "2") (pinfunction "2_2") (pintype "passive"))
      (node (ref "Z3") (pin "2") (pinfunction "A_2") (pintype "passive"))
    )
    (net (code "43") (name "Net-(Z3-C)") (class "Default")
      (node (ref "R9") (pin "2") (pinfunction "2_2") (pintype "passive"))
      (node (ref "SX1") (pin "3") (pinfunction "3_3") (pintype "passive"))
      (node (ref "Z3") (pin "1") (pinfunction "C_1") (pintype "passive"))
    )
    (net (code "44") (name "Net-(Z4-A)") (class "Default")
      (node (ref "R14") (pin "1") (pinfunction "1_1") (pintype "passive"))
      (node (ref "SX2") (pin "2") (pinfunction "2_2") (pintype "passive"))
      (node (ref "Z4") (pin "2") (pinfunction "A_2") (pintype "passive"))
    )
    (net (code "45") (name "Net-(Z4-C)") (class "Default")
      (node (ref "R15") (pin "2") (pinfunction "2_2") (pintype "passive"))
      (node (ref "SX2") (pin "3") (pinfunction "3_3") (pintype "passive"))
      (node (ref "Z4") (pin "1") (pinfunction "C_1") (pintype "passive"))
    )
    (net (code "46") (name "PE") (class "Default")
      (node (ref "J1") (pin "3") (pinfunction "3_3") (pintype "bidirectional"))
    )
    (net (code "47") (name "R+") (class "Default")
      (node (ref "R12O") (pin "1") (pinfunction "1_1") (pintype "passive"))
      (node (ref "R18O") (pin "1") (pinfunction "1_1") (pintype "passive"))
      (node (ref "R2") (pin "2") (pinfunction "2_2") (pintype "passive"))
    )
    (net (code "48") (name "R-") (class "Default")
      (node (ref "R1") (pin "2") (pinfunction "2_2") (pintype "passive"))
      (node (ref "R14O") (pin "1") (pinfunction "1_1") (pintype "passive"))
      (node (ref "R16O") (pin "1") (pinfunction "1_1") (pintype "passive"))
    )
    (net (code "49") (name "R_OUT") (class "Default")
      (node (ref "C21O") (pin "1") (pinfunction "1_1") (pintype "passive"))
      (node (ref "J3") (pin "3") (pinfunction "RING_3") (pintype "bidirectional"))
    )
    (net (code "50") (name "unconnected-(SX1-Pad9)") (class "Default")
      (node (ref "SX1") (pin "9") (pinfunction "9_9") (pintype "passive"))
    )
    (net (code "51") (name "unconnected-(SX2-Pad9)") (class "Default")
      (node (ref "SX2") (pin "9") (pinfunction "9_9") (pintype "passive"))
    )
    (net (code "52") (name "unconnected-(SX3-Pad8)") (class "Default")
      (node (ref "SX3") (pin "8") (pinfunction "8_8") (pintype "passive"))
    )
    (net (code "53") (name "unconnected-(SX4-Pad8)") (class "Default")
      (node (ref "SX4") (pin "8") (pinfunction "8_8") (pintype "passive"))
    )
  )
)
